# Halfbridges.net
KiCad netlist of a schematic drawn in Altium Designer
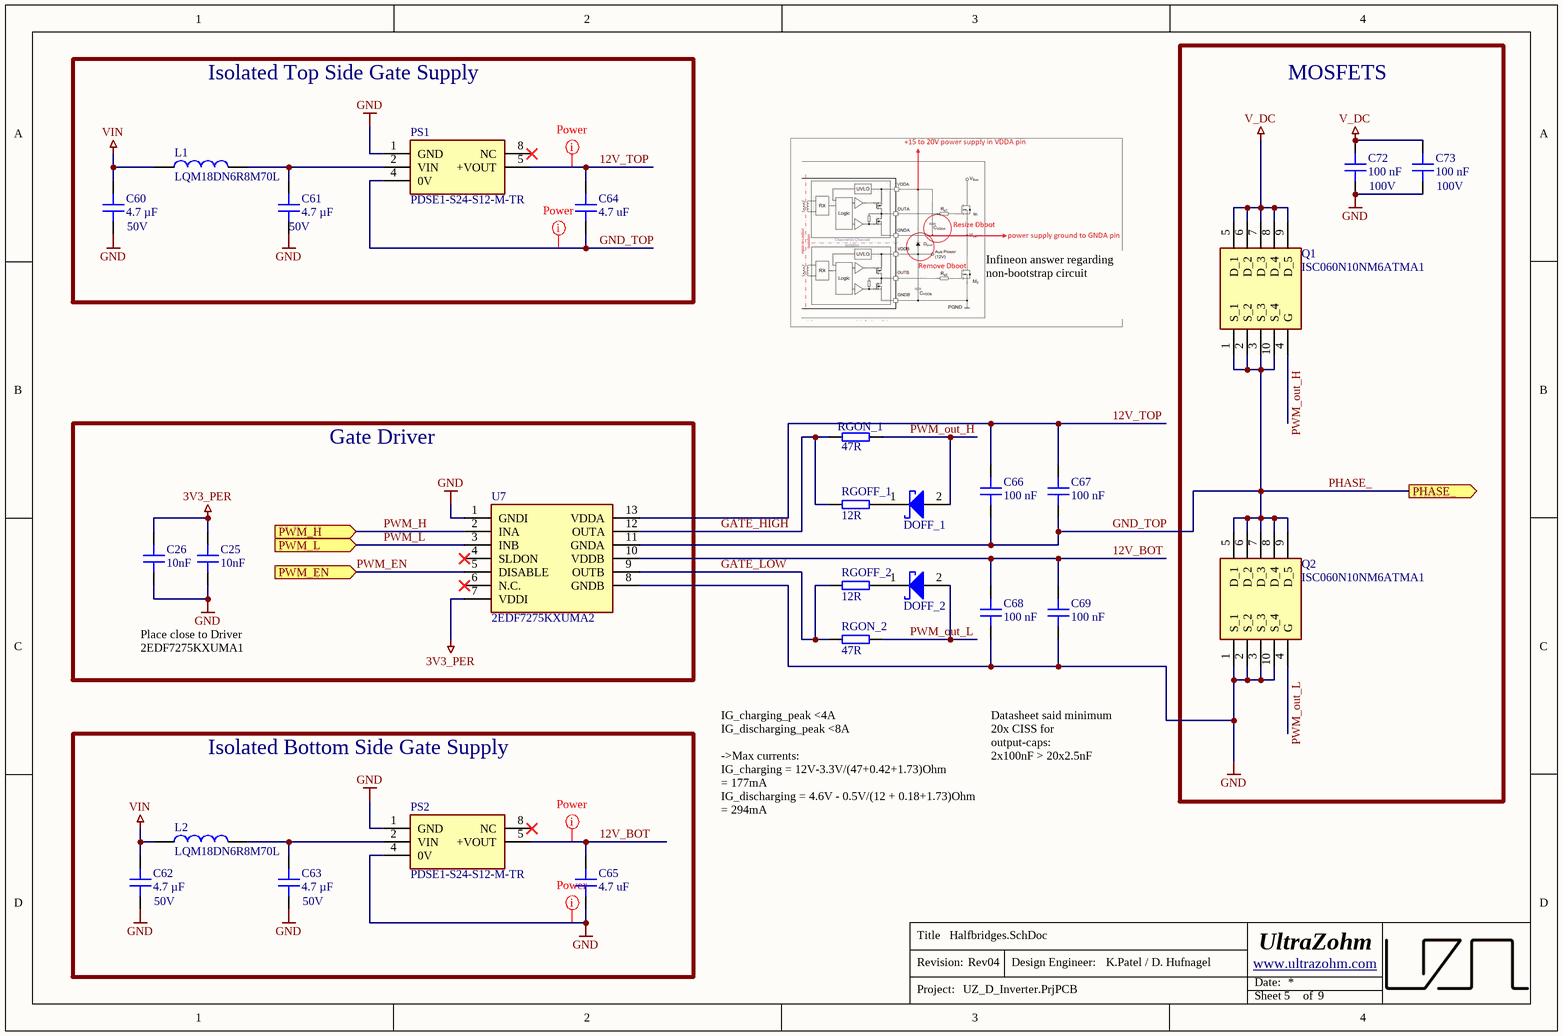
[diagram p0: Halfbridges.SchDoc]

(export (version "E")
  (design (tool "Eeschema 10.0.6"))
  (components
    (comp (ref "C25")
      (value "10nF")
      (footprint "C_0603")
      (description "50V 10nF 2X1 ±10%")
      (fields
        (field (name "MANUFACTURER PART NUMBER") "CT41G-0603-2X1-50V-0.01μF-K(N)")
        (field (name "MANUFACTURER") "TORCH")
        (field (name "CREATED FROM") "KIlhan")
      )
      (libsource (lib "user") (part "Capacitor"))
    )
    (comp (ref "C26")
      (value "10nF")
      (footprint "C_0603")
      (description "50V 10nF 2X1 ±10%")
      (fields
        (field (name "MANUFACTURER PART NUMBER") "CT41G-0603-2X1-50V-0.01μF-K(N)")
        (field (name "MANUFACTURER") "TORCH")
        (field (name "CREATED FROM") "KIlhan")
      )
      (libsource (lib "user") (part "Capacitor"))
    )
    (comp (ref "C60")
      (value "4.7 µF")
      (footprint "C_0805")
      (description "Capacitor 0805, 50 VDC, 4.7 µF, X7R")
      (fields
        (field (name "MANUFACTURER PART NUMBER") "C2012X7R1H475K125AC")
        (field (name "MANUFACTURER") "TDK")
        (field (name "CREATED FROM") "MGremer")
      )
      (libsource (lib "user") (part "Capacitor"))
    )
    (comp (ref "C61")
      (value "4.7 µF")
      (footprint "C_0805")
      (description "Capacitor 0805, 50 VDC, 4.7 µF, X7R")
      (fields
        (field (name "MANUFACTURER PART NUMBER") "C2012X7R1H475K125AC")
        (field (name "MANUFACTURER") "TDK")
        (field (name "CREATED FROM") "MGremer")
      )
      (libsource (lib "user") (part "Capacitor"))
    )
    (comp (ref "C62")
      (value "4.7 µF")
      (footprint "C_0805")
      (description "Capacitor 0805, 50 VDC, 4.7 µF, X7R")
      (fields
        (field (name "MANUFACTURER PART NUMBER") "C2012X7R1H475K125AC")
        (field (name "MANUFACTURER") "TDK")
        (field (name "CREATED FROM") "MGremer")
      )
      (libsource (lib "user") (part "Capacitor"))
    )
    (comp (ref "C63")
      (value "4.7 µF")
      (footprint "C_0805")
      (description "Capacitor 0805, 50 VDC, 4.7 µF, X7R")
      (fields
        (field (name "MANUFACTURER PART NUMBER") "C2012X7R1H475K125AC")
        (field (name "MANUFACTURER") "TDK")
        (field (name "CREATED FROM") "MGremer")
      )
      (libsource (lib "user") (part "Capacitor"))
    )
    (comp (ref "C64")
      (value "4.7 uF")
      (footprint "C_0603")
      (description "Multilayer Ceramic Capacitors MLCC - SMD/SMT RECOMMENDED ALT 810-C1608X5R1V475K")
      (fields
        (field (name "MANUFACTURER PART NUMBER") "C1608JB1V475M080AC")
        (field (name "MANUFACTURER") "TDK")
        (field (name "CREATED FROM") "KPatel")
      )
      (libsource (lib "user") (part "Capacitor"))
    )
    (comp (ref "C65")
      (value "4.7 uF")
      (footprint "C_0603")
      (description "Multilayer Ceramic Capacitors MLCC - SMD/SMT RECOMMENDED ALT 810-C1608X5R1V475K")
      (fields
        (field (name "MANUFACTURER PART NUMBER") "C1608JB1V475M080AC")
        (field (name "MANUFACTURER") "TDK")
        (field (name "CREATED FROM") "KPatel")
      )
      (libsource (lib "user") (part "Capacitor"))
    )
    (comp (ref "C66")
      (value "100 nF")
      (footprint "C_0603")
      (description "100V 100nF X7S ±10% 0603 Multilayer Ceramic Capacitors MLCC - SMD/SMT ROHS")
      (fields
        (field (name "MANUFACTURER PART NUMBER") "C1608X7S2A104KT000N")
        (field (name "MANUFACTURER") "TDK")
        (field (name "CREATED FROM") "AGeiger")
      )
      (libsource (lib "user") (part "Capacitor"))
    )
    (comp (ref "C67")
      (value "100 nF")
      (footprint "C_0603")
      (description "100V 100nF X7S ±10% 0603 Multilayer Ceramic Capacitors MLCC - SMD/SMT ROHS")
      (fields
        (field (name "MANUFACTURER PART NUMBER") "C1608X7S2A104KT000N")
        (field (name "MANUFACTURER") "TDK")
        (field (name "CREATED FROM") "AGeiger")
      )
      (libsource (lib "user") (part "Capacitor"))
    )
    (comp (ref "C68")
      (value "100 nF")
      (footprint "C_0603")
      (description "100V 100nF X7S ±10% 0603 Multilayer Ceramic Capacitors MLCC - SMD/SMT ROHS")
      (fields
        (field (name "MANUFACTURER PART NUMBER") "C1608X7S2A104KT000N")
        (field (name "MANUFACTURER") "TDK")
        (field (name "CREATED FROM") "AGeiger")
      )
      (libsource (lib "user") (part "Capacitor"))
    )
    (comp (ref "C69")
      (value "100 nF")
      (footprint "C_0603")
      (description "100V 100nF X7S ±10% 0603 Multilayer Ceramic Capacitors MLCC - SMD/SMT ROHS")
      (fields
        (field (name "MANUFACTURER PART NUMBER") "C1608X7S2A104KT000N")
        (field (name "MANUFACTURER") "TDK")
        (field (name "CREATED FROM") "AGeiger")
      )
      (libsource (lib "user") (part "Capacitor"))
    )
    (comp (ref "C72")
      (value "100 nF")
      (footprint "C_0603")
      (description "100V 100nF X7S ±10% 0603 Multilayer Ceramic Capacitors MLCC - SMD/SMT ROHS")
      (fields
        (field (name "MANUFACTURER PART NUMBER") "C1608X7S2A104KT000N")
        (field (name "MANUFACTURER") "TDK")
        (field (name "CREATED FROM") "AGeiger")
      )
      (libsource (lib "user") (part "Capacitor"))
    )
    (comp (ref "C73")
      (value "100 nF")
      (footprint "C_0603")
      (description "100V 100nF X7S ±10% 0603 Multilayer Ceramic Capacitors MLCC - SMD/SMT ROHS")
      (fields
        (field (name "MANUFACTURER PART NUMBER") "C1608X7S2A104KT000N")
        (field (name "MANUFACTURER") "TDK")
        (field (name "CREATED FROM") "AGeiger")
      )
      (libsource (lib "user") (part "Capacitor"))
    )
    (comp (ref "DOFF_1")
      (value "BAT165E6327")
      (footprint "SOD2513X110N")
      (description "Schottky Diode, 40 V, 750mA")
      (fields (field (name "MANUFACTURER") "Infineon Technologies") (field (name "CREATED FROM") "Kpatel"))
      (libsource (lib "user") (part "STPS340-Y"))
    )
    (comp (ref "DOFF_2")
      (value "BAT165E6327")
      (footprint "SOD2513X110N")
      (description "Schottky Diode, 40 V, 750mA")
      (fields (field (name "MANUFACTURER") "Infineon Technologies") (field (name "CREATED FROM") "Kpatel"))
      (libsource (lib "user") (part "STPS340-Y"))
    )
    (comp (ref "L1")
      (value "LQM18DN6R8M70L")
      (footprint "INDC1608X95N")
      (description "6.8µH, 120mA, 0603, 740mOhm, 20%")
      (fields
        (field (name "MF") "EPCOS / TDK")
        (field (name "MPN") "B82464G4154M")
        (field (name "CREATED FROM") "DHufnagel")
      )
      (libsource (lib "user") (part "B82464G4154M"))
    )
    (comp (ref "L2")
      (value "LQM18DN6R8M70L")
      (footprint "INDC1608X95N")
      (description "6.8µH, 120mA, 0603, 740mOhm, 20%")
      (fields
        (field (name "MF") "EPCOS / TDK")
        (field (name "MPN") "B82464G4154M")
        (field (name "CREATED FROM") "DHufnagel")
      )
      (libsource (lib "user") (part "B82464G4154M"))
    )
    (comp (ref "PS1")
      (value "PDSE1-S24-S12-M-TR")
      (footprint "PDSE1S24S12MTR")
      (description "Isolated, 21.6 -26.4Vin, 12V out, 1W, 84mA out")
      (fields
        (field (name "MANUFACTURER") "CUI Inc.")
        (field (name "LCSC PART NUMBER") "C6730719")
        (field (name "CREATED FROM") "DHufnagel")
      )
      (libsource (lib "user") (part "PDSE1-S24-S12-M-TR"))
    )
    (comp (ref "PS2")
      (value "PDSE1-S24-S12-M-TR")
      (footprint "PDSE1S24S12MTR")
      (description "Isolated, 21.6 -26.4Vin, 12V out, 1W, 84mA out")
      (fields
        (field (name "MANUFACTURER") "CUI Inc.")
        (field (name "LCSC PART NUMBER") "C6730719")
        (field (name "CREATED FROM") "DHufnagel")
      )
      (libsource (lib "user") (part "PDSE1-S24-S12-M-TR"))
    )
    (comp (ref "Q1")
      (value "ISC060N10NM6ATMA1")
      (footprint "ISC060N10NM6ATMA1")
      (description "Power MOSFET, n-Channel, 97A, 100V")
      (fields
        (field (name "MANUFACTURER") "Infineon Technologies")
        (field (name "LCSC PART NUMBER") "C3288847")
        (field (name "CREATED FROM") "DHufnagel")
      )
      (libsource (lib "user") (part "ISC060N10NM6ATMA1"))
    )
    (comp (ref "Q2")
      (value "ISC060N10NM6ATMA1")
      (footprint "ISC060N10NM6ATMA1")
      (description "Power MOSFET, n-Channel, 97A, 100V")
      (fields
        (field (name "MANUFACTURER") "Infineon Technologies")
        (field (name "LCSC PART NUMBER") "C3288847")
        (field (name "CREATED FROM") "DHufnagel")
      )
      (libsource (lib "user") (part "ISC060N10NM6ATMA1"))
    )
    (comp (ref "RGOFF_1")
      (value "12R")
      (footprint "RESC1609X55N")
      (description "SMD resistor E24 series")
      (fields
        (field (name "MANUFACTURER PART NUMBER") "RT0603WRC0712RL")
        (field (name "MANUFACTURER") "YAGEO")
        (field (name "CREATED FROM") "K.Patel")
      )
      (libsource (lib "user") (part "Resistor"))
    )
    (comp (ref "RGOFF_2")
      (value "12R")
      (footprint "RESC1609X55N")
      (description "SMD resistor E24 series")
      (fields
        (field (name "MANUFACTURER PART NUMBER") "RT0603WRC0712RL")
        (field (name "MANUFACTURER") "YAGEO")
        (field (name "CREATED FROM") "K.Patel")
      )
      (libsource (lib "user") (part "Resistor"))
    )
    (comp (ref "RGON_1")
      (value "47R")
      (footprint "RESC1609X55N")
      (description "SMD resistor E24 series")
      (fields
        (field (name "MANUFACTURER PART NUMBER") "RT0603WRC0747RL")
        (field (name "MANUFACTURER") "YAGEO")
        (field (name "CREATED FROM") "K.Patel")
      )
      (libsource (lib "user") (part "Resistor"))
    )
    (comp (ref "RGON_2")
      (value "47R")
      (footprint "RESC1609X55N")
      (description "SMD resistor E24 series")
      (fields
        (field (name "MANUFACTURER PART NUMBER") "RT0603WRC0747RL")
        (field (name "MANUFACTURER") "YAGEO")
        (field (name "CREATED FROM") "K.Patel")
      )
      (libsource (lib "user") (part "Resistor"))
    )
    (comp (ref "U7")
      (value "2EDF7275KXUMA2")
      (footprint "2EDF7275KXUMA1")
      (description "Gate Driver  8A, 1.5 kV, daul channel isolated gate driver")
      (fields
        (field (name "MANUFACTURER") "Infineon Technologies")
        (field (name "LCSC PART NUMBER") "C2975252")
        (field (name "CREATED FROM") "AGeiger")
      )
      (libsource (lib "user") (part "2EDF7275KXUMA1"))
    )
  )
  (nets
    (net (code "1") (name "/12V_BOT") (class "Default")
      (node (ref "C65") (pin "2") (pinfunction "2_2") (pintype "passive"))
      (node (ref "C68") (pin "2") (pinfunction "2_2") (pintype "passive"))
      (node (ref "C69") (pin "2") (pinfunction "2_2") (pintype "passive"))
      (node (ref "PS2") (pin "5") (pinfunction "+VOUT_5") (pintype "passive"))
      (node (ref "U7") (pin "10") (pinfunction "VDDB_10") (pintype "passive"))
    )
    (net (code "2") (name "/12V_TOP") (class "Default")
      (node (ref "C64") (pin "2") (pinfunction "2_2") (pintype "passive"))
      (node (ref "C66") (pin "2") (pinfunction "2_2") (pintype "passive"))
      (node (ref "C67") (pin "2") (pinfunction "2_2") (pintype "passive"))
      (node (ref "PS1") (pin "5") (pinfunction "+VOUT_5") (pintype "passive"))
      (node (ref "U7") (pin "13") (pinfunction "VDDA_13") (pintype "passive"))
    )
    (net (code "3") (name "/GATE_HIGH") (class "Default")
      (node (ref "RGOFF_1") (pin "1") (pinfunction "1_1") (pintype "passive"))
      (node (ref "RGON_1") (pin "1") (pinfunction "1_1") (pintype "passive"))
      (node (ref "U7") (pin "12") (pinfunction "OUTA_12") (pintype "passive"))
    )
    (net (code "4") (name "/GATE_LOW") (class "Default")
      (node (ref "RGOFF_2") (pin "1") (pinfunction "1_1") (pintype "passive"))
      (node (ref "RGON_2") (pin "1") (pinfunction "1_1") (pintype "passive"))
      (node (ref "U7") (pin "9") (pinfunction "OUTB_9") (pintype "passive"))
    )
    (net (code "5") (name "/GND_TOP") (class "Default")
      (node (ref "C64") (pin "1") (pinfunction "1_1") (pintype "passive"))
      (node (ref "C66") (pin "1") (pinfunction "1_1") (pintype "passive"))
      (node (ref "C67") (pin "1") (pinfunction "1_1") (pintype "passive"))
      (node (ref "PS1") (pin "4") (pinfunction "0V_4") (pintype "passive"))
      (node (ref "Q1") (pin "1") (pinfunction "S_1_1") (pintype "passive"))
      (node (ref "Q1") (pin "10") (pinfunction "S_4_10") (pintype "passive"))
      (node (ref "Q1") (pin "2") (pinfunction "S_2_2") (pintype "passive"))
      (node (ref "Q1") (pin "3") (pinfunction "S_3_3") (pintype "passive"))
      (node (ref "Q2") (pin "5") (pinfunction "D_1_5") (pintype "passive"))
      (node (ref "Q2") (pin "6") (pinfunction "D_2_6") (pintype "passive"))
      (node (ref "Q2") (pin "7") (pinfunction "D_3_7") (pintype "passive"))
      (node (ref "Q2") (pin "8") (pinfunction "D_4_8") (pintype "passive"))
      (node (ref "Q2") (pin "9") (pinfunction "D_5_9") (pintype "passive"))
      (node (ref "U7") (pin "11") (pinfunction "GNDA_11") (pintype "passive"))
    )
    (net (code "6") (name "/PWM_EN") (class "Default")
      (node (ref "U7") (pin "5") (pinfunction "DISABLE_5") (pintype "passive"))
    )
    (net (code "7") (name "/PWM_H") (class "Default")
      (node (ref "U7") (pin "2") (pinfunction "INA_2") (pintype "passive"))
    )
    (net (code "8") (name "/PWM_L") (class "Default")
      (node (ref "U7") (pin "3") (pinfunction "INB_3") (pintype "passive"))
    )
    (net (code "9") (name "/PWM_out_H") (class "Default")
      (node (ref "DOFF_1") (pin "2") (pinfunction "A_2") (pintype "passive"))
      (node (ref "Q1") (pin "4") (pinfunction "G_4") (pintype "passive"))
      (node (ref "RGON_1") (pin "2") (pinfunction "2_2") (pintype "passive"))
    )
    (net (code "10") (name "/PWM_out_L") (class "Default")
      (node (ref "DOFF_2") (pin "2") (pinfunction "A_2") (pintype "passive"))
      (node (ref "Q2") (pin "4") (pinfunction "G_4") (pintype "passive"))
      (node (ref "RGON_2") (pin "2") (pinfunction "2_2") (pintype "passive"))
    )
    (net (code "11") (name "3V3_PER") (class "Default")
      (node (ref "C25") (pin "2") (pinfunction "2_2") (pintype "passive"))
      (node (ref "C26") (pin "2") (pinfunction "2_2") (pintype "passive"))
      (node (ref "U7") (pin "7") (pinfunction "VDDI_7") (pintype "passive"))
    )
    (net (code "12") (name "GND") (class "Default")
      (node (ref "C25") (pin "1") (pinfunction "1_1") (pintype "passive"))
      (node (ref "C26") (pin "1") (pinfunction "1_1") (pintype "passive"))
      (node (ref "C60") (pin "2") (pinfunction "2_2") (pintype "passive"))
      (node (ref "C61") (pin "2") (pinfunction "2_2") (pintype "passive"))
      (node (ref "C62") (pin "2") (pinfunction "2_2") (pintype "passive"))
      (node (ref "C63") (pin "2") (pinfunction "2_2") (pintype "passive"))
      (node (ref "C65") (pin "1") (pinfunction "1_1") (pintype "passive"))
      (node (ref "C68") (pin "1") (pinfunction "1_1") (pintype "passive"))
      (node (ref "C69") (pin "1") (pinfunction "1_1") (pintype "passive"))
      (node (ref "C72") (pin "1") (pinfunction "1_1") (pintype "passive"))
      (node (ref "C73") (pin "1") (pinfunction "1_1") (pintype "passive"))
      (node (ref "PS1") (pin "1") (pinfunction "GND_1") (pintype "passive"))
      (node (ref "PS2") (pin "1") (pinfunction "GND_1") (pintype "passive"))
      (node (ref "PS2") (pin "4") (pinfunction "0V_4") (pintype "passive"))
      (node (ref "Q2") (pin "1") (pinfunction "S_1_1") (pintype "passive"))
      (node (ref "Q2") (pin "10") (pinfunction "S_4_10") (pintype "passive"))
      (node (ref "Q2") (pin "2") (pinfunction "S_2_2") (pintype "passive"))
      (node (ref "Q2") (pin "3") (pinfunction "S_3_3") (pintype "passive"))
      (node (ref "U7") (pin "1") (pinfunction "GNDI_1") (pintype "passive"))
      (node (ref "U7") (pin "8") (pinfunction "GNDB_8") (pintype "passive"))
    )
    (net (code "13") (name "Net-(DOFF_1-K)") (class "Default")
      (node (ref "DOFF_1") (pin "1") (pinfunction "K_1") (pintype "passive"))
      (node (ref "RGOFF_1") (pin "2") (pinfunction "2_2") (pintype "passive"))
    )
    (net (code "14") (name "Net-(DOFF_2-K)") (class "Default")
      (node (ref "DOFF_2") (pin "1") (pinfunction "K_1") (pintype "passive"))
      (node (ref "RGOFF_2") (pin "2") (pinfunction "2_2") (pintype "passive"))
    )
    (net (code "15") (name "Net-(PS1-VIN)") (class "Default")
      (node (ref "C61") (pin "1") (pinfunction "1_1") (pintype "passive"))
      (node (ref "L1") (pin "2") (pinfunction "2_2") (pintype "passive"))
      (node (ref "PS1") (pin "2") (pinfunction "VIN_2") (pintype "passive"))
    )
    (net (code "16") (name "Net-(PS2-VIN)") (class "Default")
      (node (ref "C63") (pin "1") (pinfunction "1_1") (pintype "passive"))
      (node (ref "L2") (pin "2") (pinfunction "2_2") (pintype "passive"))
      (node (ref "PS2") (pin "2") (pinfunction "VIN_2") (pintype "passive"))
    )
    (net (code "17") (name "VIN") (class "Default")
      (node (ref "C60") (pin "1") (pinfunction "1_1") (pintype "passive"))
      (node (ref "C62") (pin "1") (pinfunction "1_1") (pintype "passive"))
      (node (ref "L1") (pin "1") (pinfunction "1_1") (pintype "passive"))
      (node (ref "L2") (pin "1") (pinfunction "1_1") (pintype "passive"))
    )
    (net (code "18") (name "V_DC") (class "Default")
      (node (ref "C72") (pin "2") (pinfunction "2_2") (pintype "passive"))
      (node (ref "C73") (pin "2") (pinfunction "2_2") (pintype "passive"))
      (node (ref "Q1") (pin "5") (pinfunction "D_1_5") (pintype "passive"))
      (node (ref "Q1") (pin "6") (pinfunction "D_2_6") (pintype "passive"))
      (node (ref "Q1") (pin "7") (pinfunction "D_3_7") (pintype "passive"))
      (node (ref "Q1") (pin "8") (pinfunction "D_4_8") (pintype "passive"))
      (node (ref "Q1") (pin "9") (pinfunction "D_5_9") (pintype "passive"))
    )
    (net (code "19") (name "unconnected-(PS1-NC-Pad8)") (class "Default")
      (node (ref "PS1") (pin "8") (pinfunction "NC_8") (pintype "passive+no_connect"))
    )
    (net (code "20") (name "unconnected-(PS2-NC-Pad8)") (class "Default")
      (node (ref "PS2") (pin "8") (pinfunction "NC_8") (pintype "passive+no_connect"))
    )
    (net (code "21") (name "unconnected-(U7-N.C.-Pad6)") (class "Default")
      (node (ref "U7") (pin "6") (pinfunction "N.C._6") (pintype "passive+no_connect"))
    )
    (net (code "22") (name "unconnected-(U7-SLDON-Pad4)") (class "Default")
      (node (ref "U7") (pin "4") (pinfunction "SLDON_4") (pintype "passive+no_connect"))
    )
  )
)
